# simplefoc-stepmini_2024-05-25.net
KiCad netlist of a schematic drawn in Altium Designer
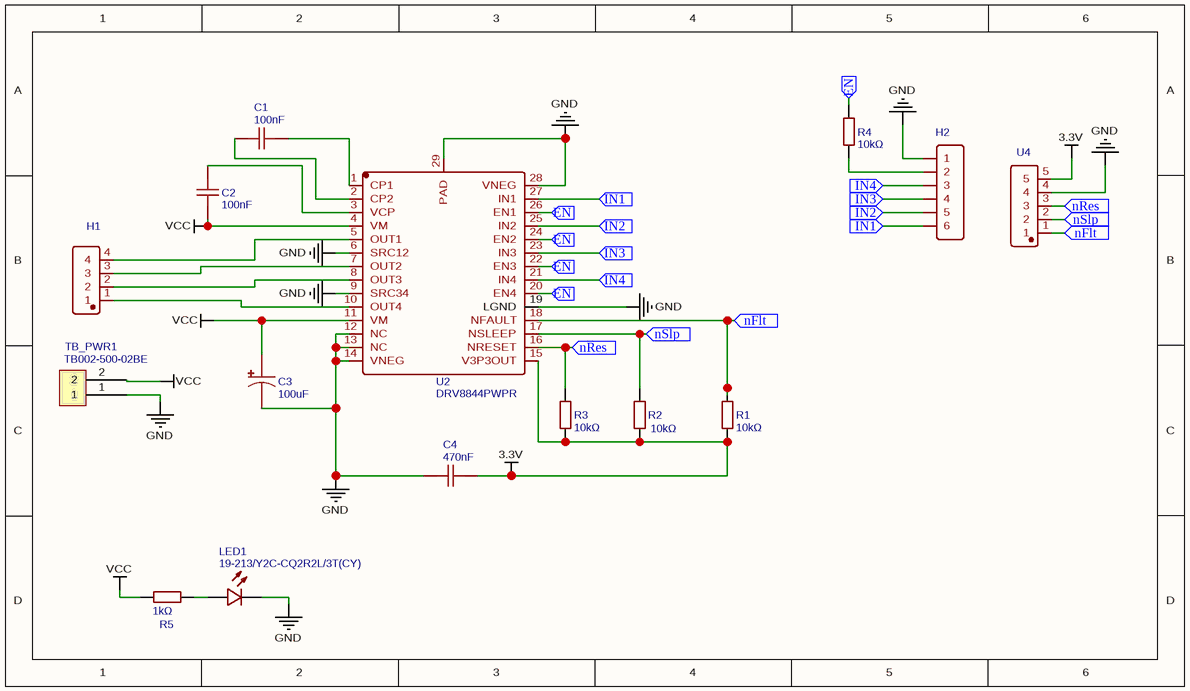
[diagram p0: simplefoc-stepmini_2024-05-25.schdoc]

(export (version "E")
  (design (tool "Eeschema 10.0.6"))
  (components
    (comp (ref "C1")
      (value "100nF")
      (fields (field (name "MANUFACTURER") "SAMSUNG") (field (name "MANUFACTURER PART") "CL10B104KB8NNNC"))
      (libsource (lib "altium-import") (part "root_0_100nF_"))
    )
    (comp (ref "C2")
      (value "100nF")
      (fields (field (name "MANUFACTURER") "SAMSUNG") (field (name "MANUFACTURER PART") "CL10B104KB8NNNC"))
      (libsource (lib "altium-import") (part "root_1_100nF_"))
    )
    (comp (ref "C3")
      (value "100uF")
      (fields
        (field (name "MANUFACTURER") "Vertical Technology")
        (field (name "MANUFACTURER PART") "VT1V101M-CRE77")
        (field (name "CONTRIBUTOR") "LCSC")
      )
      (libsource (lib "altium-import") (part "root_0_100uF_"))
    )
    (comp (ref "C4")
      (value "470nF")
      (fields
        (field (name "MANUFACTURER") "YAGEO")
        (field (name "MANUFACTURER PART") "CC0603ZRY5V6BB474")
        (field (name "CONTRIBUTOR") "LCSC")
      )
      (libsource (lib "altium-import") (part "root_0_470nF_"))
    )
    (comp (ref "H1")
      (value "KH-2.54PH180-1X4P-L11.5")
      (fields (field (name "MANUFACTURER") "kinghelm(金航标)") (field (name "CONTRIBUTOR") "LCSC"))
      (libsource (lib "altium-import") (part "root_2_KH-2.54PH180-1X4P-L11.5_"))
    )
    (comp (ref "H2")
      (value "Header-Male-2.54_1x6")
      (fields (field (name "MANUFACTURER") "BOOMELE(博穆精密)") (field (name "MANUFACTURER PART") "2.54-1x6P直针"))
      (libsource (lib "altium-import") (part "root_0_Header-Male-2.54_1x6_"))
    )
    (comp (ref "LED1")
      (value "19-213/Y2C-CQ2R2L/3T(CY)")
      (fields (field (name "MANUFACTURER") "EVERLIGHT"))
      (libsource (lib "altium-import") (part "root_0_19-213/Y2C-CQ2R2L/3T(CY)_"))
    )
    (comp (ref "R1")
      (value "10kΩ")
      (fields (field (name "MANUFACTURER") "UniOhm") (field (name "MANUFACTURER PART") "0603WAF4701T5E"))
      (libsource (lib "altium-import") (part "root_1_10kΩ_"))
    )
    (comp (ref "R2")
      (value "10kΩ")
      (fields (field (name "MANUFACTURER") "UniOhm") (field (name "MANUFACTURER PART") "0603WAF4701T5E"))
      (libsource (lib "altium-import") (part "root_1_10kΩ_"))
    )
    (comp (ref "R3")
      (value "10kΩ")
      (fields (field (name "MANUFACTURER") "UniOhm") (field (name "MANUFACTURER PART") "0603WAF4701T5E"))
      (libsource (lib "altium-import") (part "root_1_10kΩ_"))
    )
    (comp (ref "R4")
      (value "10kΩ")
      (fields (field (name "MANUFACTURER") "UniOhm") (field (name "MANUFACTURER PART") "0603WAF4701T5E"))
      (libsource (lib "altium-import") (part "root_1_10kΩ_"))
    )
    (comp (ref "R5")
      (value "1kΩ")
      (fields (field (name "MANUFACTURER") "UniOhm") (field (name "MANUFACTURER PART") "0603WAF4701T5E"))
      (libsource (lib "altium-import") (part "root_0_1kΩ_"))
    )
    (comp (ref "TB_PWR1")
      (value "TB002-500-02BE")
      (fields (field (name "CONTRIBUTOR") "the.skuric"))
      (libsource (lib "altium-import") (part "root_0_TB002-500-02BE_"))
    )
    (comp (ref "U2")
      (value "DRV8844PWPR")
      (fields (field (name "MANUFACTURER") "TI(德州仪器)") (field (name "CONTRIBUTOR") "LCSC"))
      (libsource (lib "altium-import") (part "root_0_DRV8844PWPR_"))
    )
    (comp (ref "U4")
      (value "KH-2.54FH-1X5P-H8.5")
      (fields (field (name "MANUFACTURER") "kinghelm(金航标)") (field (name "CONTRIBUTOR") "LCSC"))
      (libsource (lib "altium-import") (part "root_2_KH-2.54FH-1X5P-H8.5_"))
    )
  )
  (nets
    (net (code "1") (name "/EN") (class "Default")
      (node (ref "R4") (pin "2") (pinfunction "2_2") (pintype "passive"))
      (node (ref "U2") (pin "20") (pinfunction "EN4_20") (pintype "passive"))
      (node (ref "U2") (pin "22") (pinfunction "EN3_22") (pintype "passive"))
      (node (ref "U2") (pin "24") (pinfunction "EN2_24") (pintype "passive"))
      (node (ref "U2") (pin "26") (pinfunction "EN1_26") (pintype "passive"))
    )
    (net (code "2") (name "/IN1") (class "Default")
      (node (ref "H2") (pin "6") (pinfunction "6_6") (pintype "passive"))
      (node (ref "U2") (pin "27") (pinfunction "IN1_27") (pintype "passive"))
    )
    (net (code "3") (name "/IN2") (class "Default")
      (node (ref "H2") (pin "5") (pinfunction "5_5") (pintype "passive"))
      (node (ref "U2") (pin "25") (pinfunction "IN2_25") (pintype "passive"))
    )
    (net (code "4") (name "/IN3") (class "Default")
      (node (ref "H2") (pin "4") (pinfunction "4_4") (pintype "passive"))
      (node (ref "U2") (pin "23") (pinfunction "IN3_23") (pintype "passive"))
    )
    (net (code "5") (name "/IN4") (class "Default")
      (node (ref "H2") (pin "3") (pinfunction "3_3") (pintype "passive"))
      (node (ref "U2") (pin "21") (pinfunction "IN4_21") (pintype "passive"))
    )
    (net (code "6") (name "/nFlt") (class "Default")
      (node (ref "R1") (pin "2") (pinfunction "2_2") (pintype "passive"))
      (node (ref "U2") (pin "18") (pinfunction "NFAULT_18") (pintype "passive"))
      (node (ref "U4") (pin "1") (pinfunction "1_1") (pintype "passive"))
    )
    (net (code "7") (name "/nRes") (class "Default")
      (node (ref "R3") (pin "2") (pinfunction "2_2") (pintype "passive"))
      (node (ref "U2") (pin "16") (pinfunction "NRESET_16") (pintype "passive"))
      (node (ref "U4") (pin "3") (pinfunction "3_3") (pintype "passive"))
    )
    (net (code "8") (name "/nSlp") (class "Default")
      (node (ref "R2") (pin "2") (pinfunction "2_2") (pintype "passive"))
      (node (ref "U2") (pin "17") (pinfunction "NSLEEP_17") (pintype "passive"))
      (node (ref "U4") (pin "2") (pinfunction "2_2") (pintype "passive"))
    )
    (net (code "9") (name "3.3V") (class "Default")
      (node (ref "C4") (pin "2") (pinfunction "2_2") (pintype "passive"))
      (node (ref "R1") (pin "1") (pinfunction "1_1") (pintype "passive"))
      (node (ref "R2") (pin "1") (pinfunction "1_1") (pintype "passive"))
      (node (ref "R3") (pin "1") (pinfunction "1_1") (pintype "passive"))
      (node (ref "U2") (pin "15") (pinfunction "V3P3OUT_15") (pintype "passive"))
      (node (ref "U4") (pin "5") (pinfunction "5_5") (pintype "passive"))
    )
    (net (code "10") (name "GND") (class "Default")
      (node (ref "C3") (pin "2") (pinfunction "2_2") (pintype "passive"))
      (node (ref "C4") (pin "1") (pinfunction "1_1") (pintype "passive"))
      (node (ref "H2") (pin "1") (pinfunction "1_1") (pintype "passive"))
      (node (ref "LED1") (pin "2") (pinfunction "C_2") (pintype "passive"))
      (node (ref "TB_PWR1") (pin "1") (pinfunction "1_1") (pintype "passive"))
      (node (ref "U2") (pin "12") (pinfunction "NC_12") (pintype "passive"))
      (node (ref "U2") (pin "13") (pinfunction "NC_13") (pintype "passive"))
      (node (ref "U2") (pin "14") (pinfunction "VNEG_14") (pintype "passive"))
      (node (ref "U2") (pin "19") (pinfunction "LGND_19") (pintype "passive"))
      (node (ref "U2") (pin "28") (pinfunction "VNEG_28") (pintype "passive"))
      (node (ref "U2") (pin "29") (pinfunction "PAD_29") (pintype "passive"))
      (node (ref "U2") (pin "6") (pinfunction "SRC12_6") (pintype "passive"))
      (node (ref "U2") (pin "9") (pinfunction "SRC34_9") (pintype "passive"))
      (node (ref "U4") (pin "4") (pinfunction "4_4") (pintype "passive"))
    )
    (net (code "11") (name "Net-(H2-Pad2)") (class "Default")
      (node (ref "H2") (pin "2") (pinfunction "2_2") (pintype "passive"))
      (node (ref "R4") (pin "1") (pinfunction "1_1") (pintype "passive"))
    )
    (net (code "12") (name "Net-(LED1-A)") (class "Default")
      (node (ref "LED1") (pin "1") (pinfunction "A_1") (pintype "passive"))
      (node (ref "R5") (pin "2") (pinfunction "2_2") (pintype "passive"))
    )
    (net (code "13") (name "Net-(U2-CP1)") (class "Default")
      (node (ref "C1") (pin "2") (pinfunction "2_2") (pintype "passive"))
      (node (ref "U2") (pin "1") (pinfunction "CP1_1") (pintype "passive"))
    )
    (net (code "14") (name "Net-(U2-CP2)") (class "Default")
      (node (ref "C1") (pin "1") (pinfunction "1_1") (pintype "passive"))
      (node (ref "U2") (pin "2") (pinfunction "CP2_2") (pintype "passive"))
    )
    (net (code "15") (name "Net-(U2-OUT1)") (class "Default")
      (node (ref "H1") (pin "4") (pinfunction "4_4") (pintype "passive"))
      (node (ref "U2") (pin "5") (pinfunction "OUT1_5") (pintype "passive"))
    )
    (net (code "16") (name "Net-(U2-OUT2)") (class "Default")
      (node (ref "H1") (pin "3") (pinfunction "3_3") (pintype "passive"))
      (node (ref "U2") (pin "7") (pinfunction "OUT2_7") (pintype "passive"))
    )
    (net (code "17") (name "Net-(U2-OUT3)") (class "Default")
      (node (ref "H1") (pin "2") (pinfunction "2_2") (pintype "passive"))
      (node (ref "U2") (pin "8") (pinfunction "OUT3_8") (pintype "passive"))
    )
    (net (code "18") (name "Net-(U2-OUT4)") (class "Default")
      (node (ref "H1") (pin "1") (pinfunction "1_1") (pintype "passive"))
      (node (ref "U2") (pin "10") (pinfunction "OUT4_10") (pintype "passive"))
    )
    (net (code "19") (name "Net-(U2-VCP)") (class "Default")
      (node (ref "C2") (pin "2") (pinfunction "2_2") (pintype "passive"))
      (node (ref "U2") (pin "3") (pinfunction "VCP_3") (pintype "passive"))
    )
    (net (code "20") (name "VCC") (class "Default")
      (node (ref "C2") (pin "1") (pinfunction "1_1") (pintype "passive"))
      (node (ref "C3") (pin "1") (pinfunction "1_1") (pintype "passive"))
      (node (ref "R5") (pin "1") (pinfunction "1_1") (pintype "passive"))
      (node (ref "TB_PWR1") (pin "2") (pinfunction "2_2") (pintype "passive"))
      (node (ref "U2") (pin "11") (pinfunction "VM_11") (pintype "passive"))
      (node (ref "U2") (pin "4") (pinfunction "VM_4") (pintype "passive"))
    )
  )
)
